# StartLightGate2022.net
KiCad netlist of a schematic drawn in EAGLE
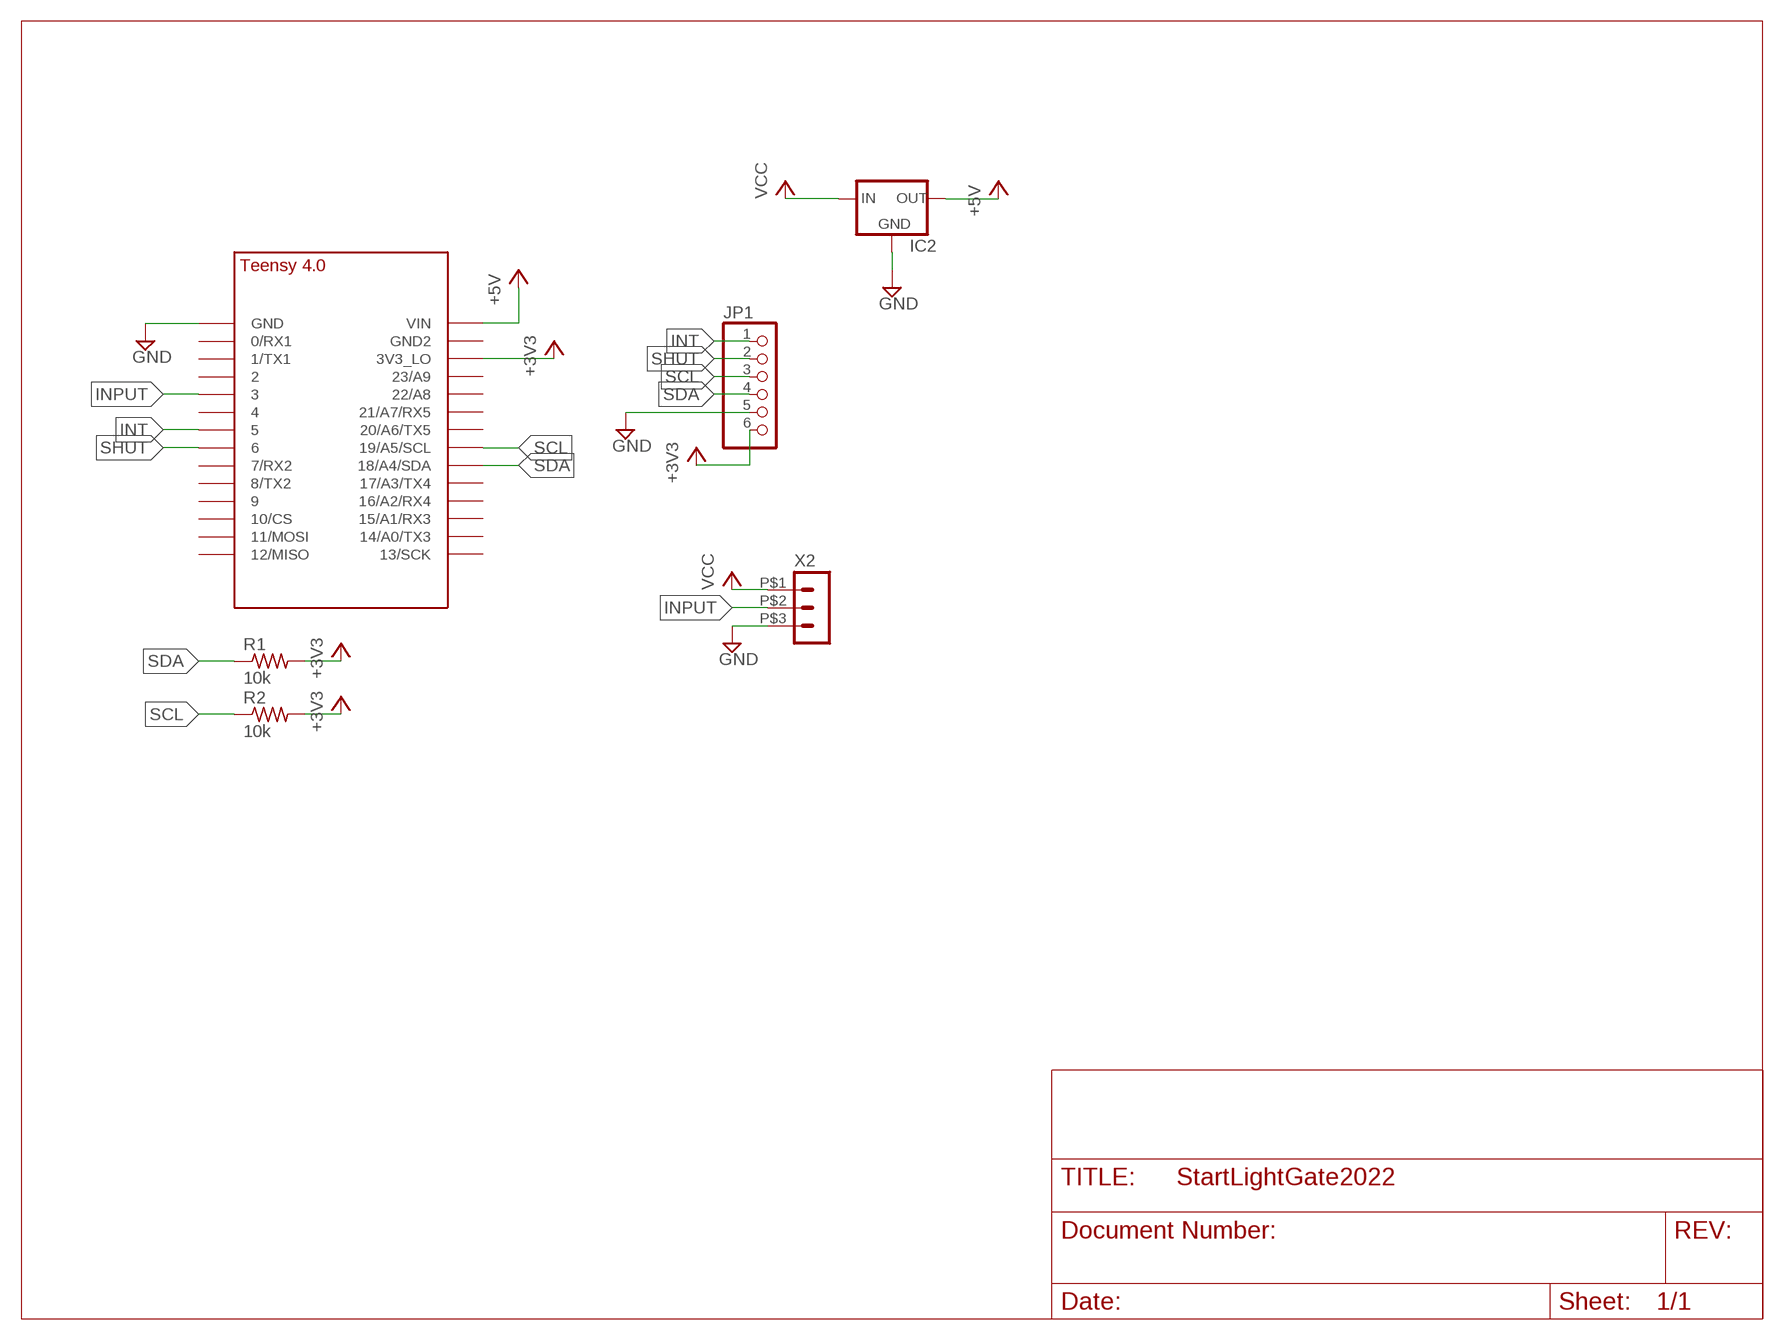
[diagram p0: schematic, sheet 1]

(export (version "E")
  (design (tool "Eeschema 10.0.6"))
  (components
    (comp (ref "IC2")
      (value "REG_5V_L7805_HOR")
      (footprint "eagle-import:TO-220-H")
      (libsource (lib "eagle-import") (part "REG_5V_L7805_HOR"))
    )
    (comp (ref "JP1")
      (value "PINHD-1X6")
      (footprint "eagle-import:1X06")
      (libsource (lib "eagle-import") (part "PINHD-1X6"))
    )
    (comp (ref "R1")
      (value "10k")
      (footprint "eagle-import:1_4W-0.4")
      (libsource (lib "eagle-import") (part "RES_AXIAL1/4W-0.4"))
    )
    (comp (ref "R2")
      (value "10k")
      (footprint "eagle-import:1_4W-0.4")
      (libsource (lib "eagle-import") (part "RES_AXIAL1/4W-0.4"))
    )
    (comp (ref "U$1")
      (value "TEENSY_4.0_SIMPLE")
      (footprint "eagle-import:TEENSY_4.0_SIMPLE")
      (libsource (lib "eagle-import") (part "TEENSY_4.0_SIMPLE"))
    )
    (comp (ref "X2")
      (value "HEADER_POS3_43650-0300")
      (footprint "eagle-import:43650-0300")
      (libsource (lib "eagle-import") (part "HEADER_POS3_?43650-0300"))
    )
  )
  (nets
    (net (code "1") (name "+3V3") (class "Default")
      (node (ref "JP1") (pin "6") (pinfunction "6_6") (pintype "passive"))
      (node (ref "R1") (pin "2") (pinfunction "2_2") (pintype "passive"))
      (node (ref "R2") (pin "2") (pinfunction "2_2") (pintype "passive"))
      (node (ref "U$1") (pin "3V3_LO") (pinfunction "3V3_LO_3V3_LO") (pintype "bidirectional"))
    )
    (net (code "2") (name "+5V") (class "Default")
      (node (ref "IC2") (pin "3") (pinfunction "OUT_3") (pintype "output"))
      (node (ref "U$1") (pin "VIN") (pinfunction "VIN_VIN") (pintype "bidirectional"))
    )
    (net (code "3") (name "GND") (class "Default")
      (node (ref "IC2") (pin "2") (pinfunction "GND_2") (pintype "input"))
      (node (ref "JP1") (pin "5") (pinfunction "5_5") (pintype "passive"))
      (node (ref "U$1") (pin "GND") (pinfunction "GND_GND") (pintype "bidirectional"))
      (node (ref "X2") (pin "P$3") (pinfunction "3_P$3") (pintype "passive"))
    )
    (net (code "4") (name "INPUT") (class "Default")
      (node (ref "U$1") (pin "3/CANTX") (pinfunction "3_3/CANTX") (pintype "bidirectional"))
      (node (ref "X2") (pin "P$2") (pinfunction "2_P$2") (pintype "passive"))
    )
    (net (code "5") (name "INT") (class "Default")
      (node (ref "JP1") (pin "1") (pinfunction "1_1") (pintype "passive"))
      (node (ref "U$1") (pin "5") (pinfunction "5_5") (pintype "bidirectional"))
    )
    (net (code "6") (name "SCL") (class "Default")
      (node (ref "JP1") (pin "3") (pinfunction "3_3") (pintype "passive"))
      (node (ref "R2") (pin "1") (pinfunction "1_1") (pintype "passive"))
      (node (ref "U$1") (pin "19/A5/SCL") (pinfunction "19/A5/SCL_19/A5/SCL") (pintype "bidirectional"))
    )
    (net (code "7") (name "SDA") (class "Default")
      (node (ref "JP1") (pin "4") (pinfunction "4_4") (pintype "passive"))
      (node (ref "R1") (pin "1") (pinfunction "1_1") (pintype "passive"))
      (node (ref "U$1") (pin "18/A4/SDA") (pinfunction "18/A4/SDA_18/A4/SDA") (pintype "bidirectional"))
    )
    (net (code "8") (name "SHUT") (class "Default")
      (node (ref "JP1") (pin "2") (pinfunction "2_2") (pintype "passive"))
      (node (ref "U$1") (pin "6") (pinfunction "6_6") (pintype "bidirectional"))
    )
    (net (code "9") (name "VCC") (class "Default")
      (node (ref "IC2") (pin "1") (pinfunction "IN_1") (pintype "input"))
      (node (ref "X2") (pin "P$1") (pinfunction "1_P$1") (pintype "passive"))
    )
    (net (code "10") (name "unconnected-(U$1-0{slash}RX1-Pad0{slash}RX)") (class "Default")
      (node (ref "U$1") (pin "0/RX") (pinfunction "0/RX1_0/RX") (pintype "bidirectional"))
    )
    (net (code "11") (name "unconnected-(U$1-1{slash}TX1-Pad1{slash}TX)") (class "Default")
      (node (ref "U$1") (pin "1/TX") (pinfunction "1/TX1_1/TX") (pintype "bidirectional"))
    )
    (net (code "12") (name "unconnected-(U$1-4-Pad4{slash}CANRX)") (class "Default")
      (node (ref "U$1") (pin "4/CANRX") (pinfunction "4_4/CANRX") (pintype "bidirectional"))
    )
    (net (code "13") (name "unconnected-(U$1-7{slash}RX2-Pad7)") (class "Default")
      (node (ref "U$1") (pin "7") (pinfunction "7/RX2_7") (pintype "bidirectional"))
    )
    (net (code "14") (name "unconnected-(U$1-8{slash}TX2-Pad8)") (class "Default")
      (node (ref "U$1") (pin "8") (pinfunction "8/TX2_8") (pintype "bidirectional"))
    )
    (net (code "15") (name "unconnected-(U$1-9-Pad9{slash}CS)") (class "Default")
      (node (ref "U$1") (pin "9/CS") (pinfunction "9_9/CS") (pintype "bidirectional"))
    )
    (net (code "16") (name "unconnected-(U$1-14{slash}A0{slash}TX3-Pad14{slash}A0)") (class "Default")
      (node (ref "U$1") (pin "14/A0") (pinfunction "14/A0/TX3_14/A0") (pintype "bidirectional"))
    )
    (net (code "17") (name "unconnected-(U$1-15{slash}A1{slash}RX3-Pad15{slash}A1)") (class "Default")
      (node (ref "U$1") (pin "15/A1") (pinfunction "15/A1/RX3_15/A1") (pintype "bidirectional"))
    )
    (net (code "18") (name "unconnected-(U$1-16{slash}A2{slash}RX4-Pad16{slash}A2)") (class "Default")
      (node (ref "U$1") (pin "16/A2") (pinfunction "16/A2/RX4_16/A2") (pintype "bidirectional"))
    )
    (net (code "19") (name "unconnected-(U$1-17{slash}A3{slash}TX4-Pad17{slash}A3)") (class "Default")
      (node (ref "U$1") (pin "17/A3") (pinfunction "17/A3/TX4_17/A3") (pintype "bidirectional"))
    )
    (net (code "20") (name "unconnected-(U$1-20{slash}A6{slash}TX5-Pad20{slash}A6)") (class "Default")
      (node (ref "U$1") (pin "20/A6") (pinfunction "20/A6/TX5_20/A6") (pintype "bidirectional"))
    )
    (net (code "21") (name "unconnected-(U$1-21{slash}A7{slash}RX5-Pad21{slash}A7)") (class "Default")
      (node (ref "U$1") (pin "21/A7") (pinfunction "21/A7/RX5_21/A7") (pintype "bidirectional"))
    )
    (net (code "22") (name "unconnected-(U$1-Pad2)") (class "Default")
      (node (ref "U$1") (pin "2") (pinfunction "2_2") (pintype "bidirectional"))
    )
    (net (code "23") (name "unconnected-(U$1-Pad10{slash}CS)") (class "Default")
      (node (ref "U$1") (pin "10/CS") (pinfunction "10/CS_10/CS") (pintype "bidirectional"))
    )
    (net (code "24") (name "unconnected-(U$1-Pad11{slash}MOSI)") (class "Default")
      (node (ref "U$1") (pin "11/MOSI") (pinfunction "11/MOSI_11/MOSI") (pintype "bidirectional"))
    )
    (net (code "25") (name "unconnected-(U$1-Pad12{slash}MISO)") (class "Default")
      (node (ref "U$1") (pin "12/MISO") (pinfunction "12/MISO_12/MISO") (pintype "bidirectional"))
    )
    (net (code "26") (name "unconnected-(U$1-Pad13{slash}SCK)") (class "Default")
      (node (ref "U$1") (pin "13/SCK") (pinfunction "13/SCK_13/SCK") (pintype "bidirectional"))
    )
    (net (code "27") (name "unconnected-(U$1-Pad22{slash}A8)") (class "Default")
      (node (ref "U$1") (pin "22/A8") (pinfunction "22/A8_22/A8") (pintype "bidirectional"))
    )
    (net (code "28") (name "unconnected-(U$1-Pad23{slash}A9)") (class "Default")
      (node (ref "U$1") (pin "23/A9") (pinfunction "23/A9_23/A9") (pintype "bidirectional"))
    )
    (net (code "29") (name "unconnected-(U$1-PadGND2)") (class "Default")
      (node (ref "U$1") (pin "GND2") (pinfunction "GND2_GND2") (pintype "bidirectional"))
    )
  )
)
